# ESP_notifier.net
KiCad netlist of a schematic drawn in EAGLE
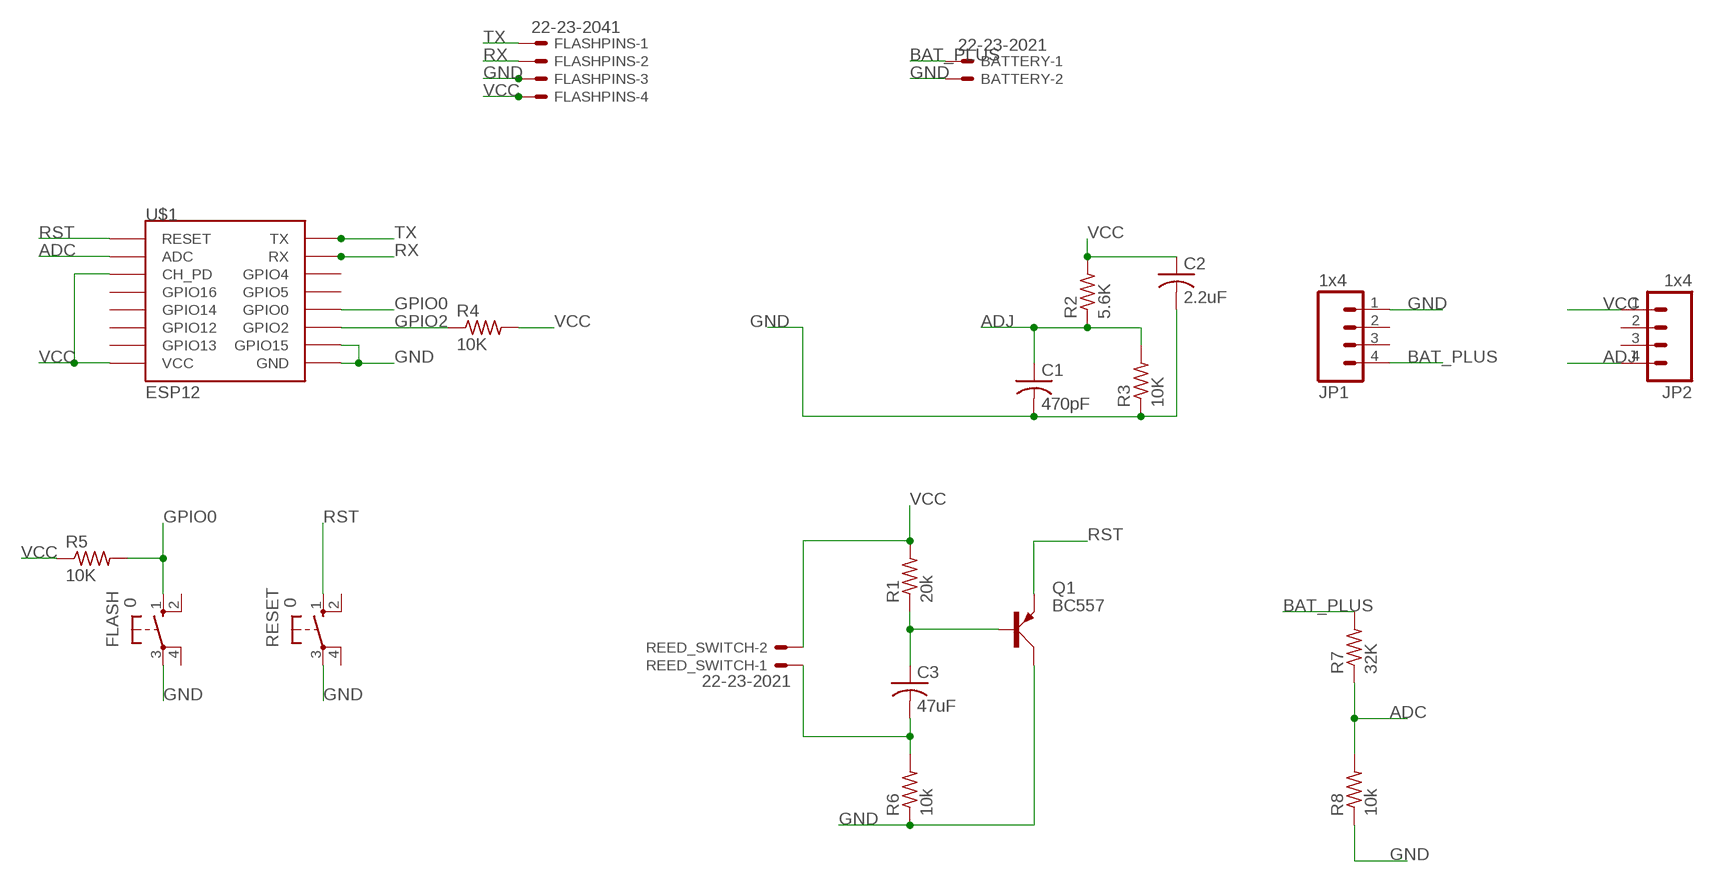
[diagram p0: schematic, sheet 1]

(export (version "E")
  (design (tool "Eeschema 10.0.6"))
  (components
    (comp (ref "BATTERY")
      (value "22-23-2021")
      (footprint "eagle-import:22-23-2021")
      (fields (field (name "MF") "MOLEX"))
      (libsource (lib "eagle-import") (part "22-23-2021"))
    )
    (comp (ref "C1")
      (value "470pF")
      (footprint "eagle-import:C075-032X103")
      (libsource (lib "eagle-import") (part "C-US075-032X103"))
    )
    (comp (ref "C2")
      (value "2.2uF")
      (footprint "eagle-import:C075-032X103")
      (libsource (lib "eagle-import") (part "C-US075-032X103"))
    )
    (comp (ref "C3")
      (value "47uF")
      (footprint "eagle-import:C075-032X103")
      (libsource (lib "eagle-import") (part "C-US075-032X103"))
    )
    (comp (ref "FLASH")
      (value "0")
      (footprint "eagle-import:B3F-10XX")
      (fields (field (name "MPN") "B3F-1000"))
      (libsource (lib "eagle-import") (part "10-XX"))
    )
    (comp (ref "FLASHPINS")
      (value "22-23-2041")
      (footprint "eagle-import:22-23-2041")
      (fields (field (name "MF") "MOLEX"))
      (libsource (lib "eagle-import") (part "22-23-2041"))
    )
    (comp (ref "JP1")
      (value "1x4")
      (footprint "eagle-import:1X04_NO_SILK")
      (libsource (lib "eagle-import") (part "M041X04_NO_SILK"))
    )
    (comp (ref "JP2")
      (value "1x4")
      (footprint "eagle-import:1X04_NO_SILK_ALL_ROUND")
      (libsource (lib "eagle-import") (part "M04NO_SILK_ALL_ROUND"))
    )
    (comp (ref "Q1")
      (value "BC557")
      (footprint "eagle-import:SOT54A")
      (libsource (lib "eagle-import") (part "BC557"))
    )
    (comp (ref "R1")
      (value "20k")
      (footprint "eagle-import:0207_9")
      (libsource (lib "eagle-import") (part "R-US_0207/9"))
    )
    (comp (ref "R2")
      (value "5.6K")
      (footprint "eagle-import:0207_9")
      (libsource (lib "eagle-import") (part "R-US_0207/9"))
    )
    (comp (ref "R3")
      (value "10K")
      (footprint "eagle-import:0207_9")
      (libsource (lib "eagle-import") (part "R-US_0207/9"))
    )
    (comp (ref "R4")
      (value "10K")
      (footprint "eagle-import:0207_9")
      (libsource (lib "eagle-import") (part "R-US_0207/9"))
    )
    (comp (ref "R5")
      (value "10K")
      (footprint "eagle-import:0207_9")
      (libsource (lib "eagle-import") (part "R-US_0207/9"))
    )
    (comp (ref "R6")
      (value "10k")
      (footprint "eagle-import:0207_9")
      (libsource (lib "eagle-import") (part "R-US_0207/9"))
    )
    (comp (ref "R7")
      (value "32K")
      (footprint "eagle-import:0207_9")
      (libsource (lib "eagle-import") (part "R-US_0207/9"))
    )
    (comp (ref "R8")
      (value "10k")
      (footprint "eagle-import:0207_9")
      (libsource (lib "eagle-import") (part "R-US_0207/9"))
    )
    (comp (ref "REED_SWITCH")
      (value "22-23-2021")
      (footprint "eagle-import:22-23-2021")
      (fields (field (name "MF") "MOLEX"))
      (libsource (lib "eagle-import") (part "22-23-2021"))
    )
    (comp (ref "RESET")
      (value "0")
      (footprint "eagle-import:B3F-10XX")
      (fields (field (name "MPN") "B3F-1000"))
      (libsource (lib "eagle-import") (part "10-XX"))
    )
    (comp (ref "U$1")
      (value "ESP12")
      (footprint "eagle-import:ESP12")
      (libsource (lib "eagle-import") (part "ESP12"))
    )
  )
  (nets
    (net (code "1") (name "/ADC") (class "Default")
      (node (ref "R7") (pin "1") (pinfunction "1_1") (pintype "passive"))
      (node (ref "R8") (pin "2") (pinfunction "2_2") (pintype "passive"))
      (node (ref "U$1") (pin "ADC") (pinfunction "ADC_ADC") (pintype "bidirectional"))
    )
    (net (code "2") (name "/ADJ") (class "Default")
      (node (ref "C1") (pin "1") (pinfunction "1_1") (pintype "passive"))
      (node (ref "JP2") (pin "4") (pinfunction "4_4") (pintype "passive"))
      (node (ref "R2") (pin "1") (pinfunction "1_1") (pintype "passive"))
      (node (ref "R3") (pin "2") (pinfunction "2_2") (pintype "passive"))
    )
    (net (code "3") (name "/BAT_PLUS") (class "Default")
      (node (ref "BATTERY") (pin "1") (pinfunction "S_1") (pintype "passive"))
      (node (ref "JP1") (pin "4") (pinfunction "4_4") (pintype "passive"))
      (node (ref "R7") (pin "2") (pinfunction "2_2") (pintype "passive"))
    )
    (net (code "4") (name "/GND") (class "Default")
      (node (ref "BATTERY") (pin "2") (pinfunction "S_2") (pintype "passive"))
      (node (ref "C1") (pin "2") (pinfunction "2_2") (pintype "passive"))
      (node (ref "C2") (pin "2") (pinfunction "2_2") (pintype "passive"))
      (node (ref "FLASH") (pin "3") (pinfunction "P_3") (pintype "passive"))
      (node (ref "FLASHPINS") (pin "3") (pinfunction "S_3") (pintype "passive"))
      (node (ref "JP1") (pin "1") (pinfunction "1_1") (pintype "passive"))
      (node (ref "Q1") (pin "C") (pinfunction "C_C") (pintype "passive"))
      (node (ref "R3") (pin "1") (pinfunction "1_1") (pintype "passive"))
      (node (ref "R6") (pin "1") (pinfunction "1_1") (pintype "passive"))
      (node (ref "R8") (pin "1") (pinfunction "1_1") (pintype "passive"))
      (node (ref "RESET") (pin "3") (pinfunction "P_3") (pintype "passive"))
      (node (ref "U$1") (pin "GND") (pinfunction "GND_GND") (pintype "bidirectional"))
      (node (ref "U$1") (pin "GPIO15") (pinfunction "GPIO15_GPIO15") (pintype "bidirectional"))
    )
    (net (code "5") (name "/GPIO0") (class "Default")
      (node (ref "FLASH") (pin "1") (pinfunction "S_1") (pintype "passive"))
      (node (ref "R5") (pin "2") (pinfunction "2_2") (pintype "passive"))
      (node (ref "U$1") (pin "GPIO0") (pinfunction "GPIO0_GPIO0") (pintype "bidirectional"))
    )
    (net (code "6") (name "/GPIO2") (class "Default")
      (node (ref "R4") (pin "1") (pinfunction "1_1") (pintype "passive"))
      (node (ref "U$1") (pin "GPIO2") (pinfunction "GPIO2_GPIO2") (pintype "bidirectional"))
    )
    (net (code "7") (name "/RST") (class "Default")
      (node (ref "Q1") (pin "E") (pinfunction "E_E") (pintype "passive"))
      (node (ref "RESET") (pin "1") (pinfunction "S_1") (pintype "passive"))
      (node (ref "U$1") (pin "RESET") (pinfunction "RESET_RESET") (pintype "bidirectional"))
    )
    (net (code "8") (name "/RX") (class "Default")
      (node (ref "FLASHPINS") (pin "2") (pinfunction "S_2") (pintype "passive"))
      (node (ref "U$1") (pin "RX") (pinfunction "RX_RX") (pintype "bidirectional"))
    )
    (net (code "9") (name "/TX") (class "Default")
      (node (ref "FLASHPINS") (pin "1") (pinfunction "S_1") (pintype "passive"))
      (node (ref "U$1") (pin "TX") (pinfunction "TX_TX") (pintype "bidirectional"))
    )
    (net (code "10") (name "/VCC") (class "Default")
      (node (ref "C2") (pin "1") (pinfunction "1_1") (pintype "passive"))
      (node (ref "FLASHPINS") (pin "4") (pinfunction "S_4") (pintype "passive"))
      (node (ref "JP2") (pin "1") (pinfunction "1_1") (pintype "passive"))
      (node (ref "R1") (pin "2") (pinfunction "2_2") (pintype "passive"))
      (node (ref "R2") (pin "2") (pinfunction "2_2") (pintype "passive"))
      (node (ref "R4") (pin "2") (pinfunction "2_2") (pintype "passive"))
      (node (ref "R5") (pin "1") (pinfunction "1_1") (pintype "passive"))
      (node (ref "REED_SWITCH") (pin "2") (pinfunction "S_2") (pintype "passive"))
      (node (ref "U$1") (pin "CH_PD") (pinfunction "CH_PD_CH_PD") (pintype "bidirectional"))
      (node (ref "U$1") (pin "VCC") (pinfunction "VCC_VCC") (pintype "bidirectional"))
    )
    (net (code "11") (name "Net-(C3-Pad1)") (class "Default")
      (node (ref "C3") (pin "1") (pinfunction "1_1") (pintype "passive"))
      (node (ref "Q1") (pin "B") (pinfunction "B_B") (pintype "passive"))
      (node (ref "R1") (pin "1") (pinfunction "1_1") (pintype "passive"))
    )
    (net (code "12") (name "Net-(REED_SWITCHA-S)") (class "Default")
      (node (ref "C3") (pin "2") (pinfunction "2_2") (pintype "passive"))
      (node (ref "R6") (pin "2") (pinfunction "2_2") (pintype "passive"))
      (node (ref "REED_SWITCH") (pin "1") (pinfunction "S_1") (pintype "passive"))
    )
    (net (code "13") (name "unconnected-(FLASH-P1-Pad4)") (class "Default")
      (node (ref "FLASH") (pin "4") (pinfunction "P1_4") (pintype "passive"))
    )
    (net (code "14") (name "unconnected-(FLASH-S1-Pad2)") (class "Default")
      (node (ref "FLASH") (pin "2") (pinfunction "S1_2") (pintype "passive"))
    )
    (net (code "15") (name "unconnected-(JP1-Pad2)") (class "Default")
      (node (ref "JP1") (pin "2") (pinfunction "2_2") (pintype "passive"))
    )
    (net (code "16") (name "unconnected-(JP1-Pad3)") (class "Default")
      (node (ref "JP1") (pin "3") (pinfunction "3_3") (pintype "passive"))
    )
    (net (code "17") (name "unconnected-(JP2-Pad2)") (class "Default")
      (node (ref "JP2") (pin "2") (pinfunction "2_2") (pintype "passive"))
    )
    (net (code "18") (name "unconnected-(JP2-Pad3)") (class "Default")
      (node (ref "JP2") (pin "3") (pinfunction "3_3") (pintype "passive"))
    )
    (net (code "19") (name "unconnected-(RESET-P1-Pad4)") (class "Default")
      (node (ref "RESET") (pin "4") (pinfunction "P1_4") (pintype "passive"))
    )
    (net (code "20") (name "unconnected-(RESET-S1-Pad2)") (class "Default")
      (node (ref "RESET") (pin "2") (pinfunction "S1_2") (pintype "passive"))
    )
    (net (code "21") (name "unconnected-(U$1-PadGPIO4)") (class "Default")
      (node (ref "U$1") (pin "GPIO4") (pinfunction "GPIO4_GPIO4") (pintype "bidirectional"))
    )
    (net (code "22") (name "unconnected-(U$1-PadGPIO5)") (class "Default")
      (node (ref "U$1") (pin "GPIO5") (pinfunction "GPIO5_GPIO5") (pintype "bidirectional"))
    )
    (net (code "23") (name "unconnected-(U$1-PadGPIO12)") (class "Default")
      (node (ref "U$1") (pin "GPIO12") (pinfunction "GPIO12_GPIO12") (pintype "bidirectional"))
    )
    (net (code "24") (name "unconnected-(U$1-PadGPIO13)") (class "Default")
      (node (ref "U$1") (pin "GPIO13") (pinfunction "GPIO13_GPIO13") (pintype "bidirectional"))
    )
    (net (code "25") (name "unconnected-(U$1-PadGPIO14)") (class "Default")
      (node (ref "U$1") (pin "GPIO14") (pinfunction "GPIO14_GPIO14") (pintype "bidirectional"))
    )
    (net (code "26") (name "unconnected-(U$1-PadGPIO16)") (class "Default")
      (node (ref "U$1") (pin "GPIO16") (pinfunction "GPIO16_GPIO16") (pintype "bidirectional"))
    )
  )
)
